# Kit_STM32.net
KiCad netlist of a schematic drawn in Altium Designer
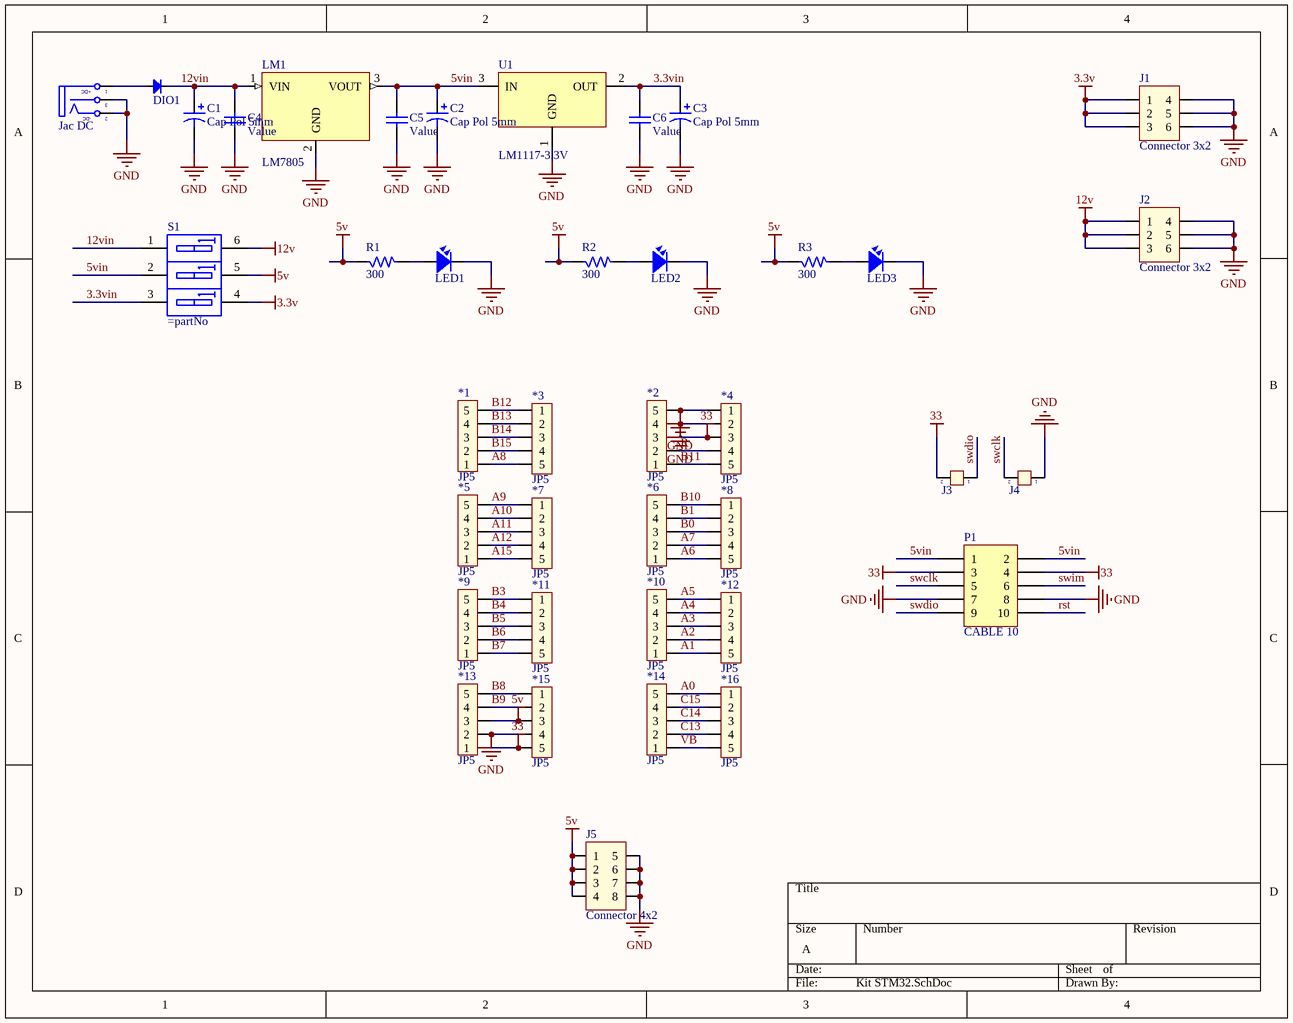
[diagram p0: Kit STM32.SchDoc]

(export (version "E")
  (design (tool "Eeschema 10.0.6"))
  (components
    (comp (ref "*1") (value "JP5") (footprint "JP5") (libsource (lib "") (part "JP5_1")))
    (comp (ref "*2") (value "JP5") (footprint "JP5") (libsource (lib "") (part "JP5_1")))
    (comp (ref "*3") (value "JP5") (footprint "JP5") (libsource (lib "Cty1") (part "JP5")))
    (comp (ref "*4") (value "JP5") (footprint "JP5") (libsource (lib "Cty1") (part "JP5")))
    (comp (ref "*5") (value "JP5") (footprint "JP5") (libsource (lib "") (part "JP5_1")))
    (comp (ref "*6") (value "JP5") (footprint "JP5") (libsource (lib "") (part "JP5_1")))
    (comp (ref "*7") (value "JP5") (footprint "JP5") (libsource (lib "Cty1") (part "JP5")))
    (comp (ref "*8") (value "JP5") (footprint "JP5") (libsource (lib "Cty1") (part "JP5")))
    (comp (ref "*9") (value "JP5") (footprint "JP5") (libsource (lib "") (part "JP5_1")))
    (comp (ref "*10") (value "JP5") (footprint "JP5") (libsource (lib "") (part "JP5_1")))
    (comp (ref "*11") (value "JP5") (footprint "JP5") (libsource (lib "Cty1") (part "JP5")))
    (comp (ref "*12") (value "JP5") (footprint "JP5") (libsource (lib "Cty1") (part "JP5")))
    (comp (ref "*13") (value "JP5") (footprint "JP5") (libsource (lib "") (part "JP5_1")))
    (comp (ref "*14") (value "JP5") (footprint "JP5") (libsource (lib "") (part "JP5_1")))
    (comp (ref "*15") (value "JP5") (footprint "JP5") (libsource (lib "Cty1") (part "JP5")))
    (comp (ref "*16") (value "JP5") (footprint "JP5") (libsource (lib "Cty1") (part "JP5")))
    (comp (ref "C1")
      (value "Cap Pol 5mm")
      (footprint "C5mm")
      (description "Polarized Capacitor (Axial)")
      (fields (field (name "PUBLISHER") "Altium Limited"))
      (libsource (lib "Cty1") (part "Cap Pol 5mm"))
    )
    (comp (ref "C2")
      (value "Cap Pol 5mm")
      (footprint "C5mm")
      (description "Polarized Capacitor (Axial)")
      (fields (field (name "PUBLISHER") "Altium Limited"))
      (libsource (lib "Cty1") (part "Cap Pol 5mm"))
    )
    (comp (ref "C3")
      (value "Cap Pol 5mm")
      (footprint "C5mm")
      (description "Polarized Capacitor (Axial)")
      (fields (field (name "PUBLISHER") "Altium Limited"))
      (libsource (lib "Cty1") (part "Cap Pol 5mm"))
    )
    (comp (ref "C4") (value "Value") (footprint "C1206") (libsource (lib "Cty1") (part "Cap SMD 1206")))
    (comp (ref "C5") (value "Value") (footprint "C1206") (libsource (lib "Cty1") (part "Cap SMD 1206")))
    (comp (ref "C6") (value "Value") (footprint "C1206") (libsource (lib "Cty1") (part "Cap SMD 1206")))
    (comp (ref "DIO1")
      (value "Diode SMD")
      (footprint "DIO-SMD-106")
      (description "Default Diode")
      (fields (field (name "PUBLISHER") "Altium Limited"))
      (libsource (lib "LIBRARY") (part "Diode SMD"))
    )
    (comp (ref "J1") (value "Connector 3x2") (footprint "JP3x2") (libsource (lib "Cty1") (part "JP3x2")))
    (comp (ref "J2") (value "Connector 3x2") (footprint "JP3x2") (libsource (lib "Cty1") (part "JP3x2")))
    (comp (ref "J3") (value "Jumper 2") (footprint "JP2") (libsource (lib "Cty1") (part "JP 2")))
    (comp (ref "J4") (value "Jumper 2") (footprint "JP2") (libsource (lib "Cty1") (part "JP 2")))
    (comp (ref "J5") (value "Connector 4x2") (footprint "JP4x2") (libsource (lib "Cty1") (part "JP4x2")))
    (comp (ref "JDC1")
      (value "Jac DC")
      (footprint "DC-IN")
      (description "Jac DC input")
      (libsource (lib "syhaunguyen") (part "DCIN"))
    )
    (comp (ref "LED1") (value "LED") (footprint "LED 3512") (libsource (lib "LIBRARY") (part "LED SMD")))
    (comp (ref "LED2") (value "LED") (footprint "LED 3512") (libsource (lib "LIBRARY") (part "LED SMD")))
    (comp (ref "LED3") (value "LED") (footprint "LED 3512") (libsource (lib "LIBRARY") (part "LED SMD")))
    (comp (ref "LM1")
      (value "LM7805")
      (footprint "QTO-220H3")
      (description "TO-220")
      (libsource (lib "Cty1") (part "LM7805"))
    )
    (comp (ref "P1")
      (value "CABLE 10")
      (footprint "CABLE 10")
      (description "Header, 5-Pin, Dual row")
      (fields (field (name "PUBLISHER") "Altium Limited"))
      (libsource (lib "Cty1") (part "CABLE 10"))
    )
    (comp (ref "R1")
      (value "300")
      (footprint "SM-1206")
      (description "Resistor 1/4W")
      (libsource (lib "Cty1") (part "Res"))
    )
    (comp (ref "R2")
      (value "300")
      (footprint "SM-1206")
      (description "Resistor 1/4W")
      (libsource (lib "Cty1") (part "Res"))
    )
    (comp (ref "R3")
      (value "300")
      (footprint "SM-1206")
      (description "Resistor 1/4W")
      (libsource (lib "Cty1") (part "Res"))
    )
    (comp (ref "S1")
      (value "~")
      (footprint "SW-DIP3")
      (description "WS-DITV 2.54 mm small compact THT flat actuator with top tape")
      (fields
        (field (name "MANUFACTURER") "Wurth Elektronik")
        (field (name "PART NO.") "418127160901")
        (field (name "CREATED BY") "Baojun Chen")
      )
      (libsource (lib "LIBRARY") (part "SWDIP3"))
    )
    (comp (ref "U1")
      (value "LM1117-3.3V")
      (footprint "SOT223-4N")
      (description "800mA Low-Dropout Linear Regulator")
      (fields (field (name "CREATOR") "Nguyen Ba Bien"))
      (libsource (lib "Cty1") (part "LM1117"))
    )
  )
  (nets
    (net (code "1") (name "/3.3vin") (class "Default")
      (node (ref "C3") (pin "1") (pinfunction "1_1") (pintype "passive"))
      (node (ref "C6") (pin "2") (pinfunction "2_2") (pintype "passive"))
      (node (ref "S1") (pin "3") (pinfunction "3_3") (pintype "passive"))
      (node (ref "U1") (pin "2") (pinfunction "OUT_2") (pintype "passive"))
    )
    (net (code "2") (name "/5vin") (class "Default")
      (node (ref "C2") (pin "1") (pinfunction "1_1") (pintype "passive"))
      (node (ref "C5") (pin "2") (pinfunction "2_2") (pintype "passive"))
      (node (ref "LM1") (pin "3") (pinfunction "VOUT_3") (pintype "output"))
      (node (ref "P1") (pin "1") (pinfunction "1_1") (pintype "passive"))
      (node (ref "P1") (pin "2") (pinfunction "2_2") (pintype "passive"))
      (node (ref "S1") (pin "2") (pinfunction "2_2") (pintype "passive"))
      (node (ref "U1") (pin "3") (pinfunction "IN_3") (pintype "passive"))
    )
    (net (code "3") (name "/12vin") (class "Default")
      (node (ref "C1") (pin "1") (pinfunction "1_1") (pintype "passive"))
      (node (ref "C4") (pin "2") (pinfunction "2_2") (pintype "passive"))
      (node (ref "DIO1") (pin "2") (pinfunction "K_2") (pintype "passive"))
      (node (ref "LM1") (pin "1") (pinfunction "VIN_1") (pintype "input"))
      (node (ref "S1") (pin "1") (pinfunction "1_1") (pintype "passive"))
    )
    (net (code "4") (name "/A0") (class "Default")
      (node (ref "*14") (pin "5") (pinfunction "5_5") (pintype "passive"))
      (node (ref "*16") (pin "1") (pinfunction "1_1") (pintype "passive"))
    )
    (net (code "5") (name "/A1") (class "Default")
      (node (ref "*10") (pin "1") (pinfunction "1_1") (pintype "passive"))
      (node (ref "*12") (pin "5") (pinfunction "5_5") (pintype "passive"))
    )
    (net (code "6") (name "/A2") (class "Default")
      (node (ref "*10") (pin "2") (pinfunction "2_2") (pintype "passive"))
      (node (ref "*12") (pin "4") (pinfunction "4_4") (pintype "passive"))
    )
    (net (code "7") (name "/A3") (class "Default")
      (node (ref "*10") (pin "3") (pinfunction "3_3") (pintype "passive"))
      (node (ref "*12") (pin "3") (pinfunction "3_3") (pintype "passive"))
    )
    (net (code "8") (name "/A4") (class "Default")
      (node (ref "*10") (pin "4") (pinfunction "4_4") (pintype "passive"))
      (node (ref "*12") (pin "2") (pinfunction "2_2") (pintype "passive"))
    )
    (net (code "9") (name "/A5") (class "Default")
      (node (ref "*10") (pin "5") (pinfunction "5_5") (pintype "passive"))
      (node (ref "*12") (pin "1") (pinfunction "1_1") (pintype "passive"))
    )
    (net (code "10") (name "/A6") (class "Default")
      (node (ref "*6") (pin "1") (pinfunction "1_1") (pintype "passive"))
      (node (ref "*8") (pin "5") (pinfunction "5_5") (pintype "passive"))
    )
    (net (code "11") (name "/A7") (class "Default")
      (node (ref "*6") (pin "2") (pinfunction "2_2") (pintype "passive"))
      (node (ref "*8") (pin "4") (pinfunction "4_4") (pintype "passive"))
    )
    (net (code "12") (name "/A8") (class "Default")
      (node (ref "*1") (pin "1") (pinfunction "1_1") (pintype "passive"))
      (node (ref "*3") (pin "5") (pinfunction "5_5") (pintype "passive"))
    )
    (net (code "13") (name "/A9") (class "Default")
      (node (ref "*5") (pin "5") (pinfunction "5_5") (pintype "passive"))
      (node (ref "*7") (pin "1") (pinfunction "1_1") (pintype "passive"))
    )
    (net (code "14") (name "/A10") (class "Default")
      (node (ref "*5") (pin "4") (pinfunction "4_4") (pintype "passive"))
      (node (ref "*7") (pin "2") (pinfunction "2_2") (pintype "passive"))
    )
    (net (code "15") (name "/A11") (class "Default")
      (node (ref "*5") (pin "3") (pinfunction "3_3") (pintype "passive"))
      (node (ref "*7") (pin "3") (pinfunction "3_3") (pintype "passive"))
    )
    (net (code "16") (name "/A12") (class "Default")
      (node (ref "*5") (pin "2") (pinfunction "2_2") (pintype "passive"))
      (node (ref "*7") (pin "4") (pinfunction "4_4") (pintype "passive"))
    )
    (net (code "17") (name "/A15") (class "Default")
      (node (ref "*5") (pin "1") (pinfunction "1_1") (pintype "passive"))
      (node (ref "*7") (pin "5") (pinfunction "5_5") (pintype "passive"))
    )
    (net (code "18") (name "/B0") (class "Default")
      (node (ref "*6") (pin "3") (pinfunction "3_3") (pintype "passive"))
      (node (ref "*8") (pin "3") (pinfunction "3_3") (pintype "passive"))
    )
    (net (code "19") (name "/B1") (class "Default")
      (node (ref "*6") (pin "4") (pinfunction "4_4") (pintype "passive"))
      (node (ref "*8") (pin "2") (pinfunction "2_2") (pintype "passive"))
    )
    (net (code "20") (name "/B3") (class "Default")
      (node (ref "*11") (pin "1") (pinfunction "1_1") (pintype "passive"))
      (node (ref "*9") (pin "5") (pinfunction "5_5") (pintype "passive"))
    )
    (net (code "21") (name "/B4") (class "Default")
      (node (ref "*11") (pin "2") (pinfunction "2_2") (pintype "passive"))
      (node (ref "*9") (pin "4") (pinfunction "4_4") (pintype "passive"))
    )
    (net (code "22") (name "/B5") (class "Default")
      (node (ref "*11") (pin "3") (pinfunction "3_3") (pintype "passive"))
      (node (ref "*9") (pin "3") (pinfunction "3_3") (pintype "passive"))
    )
    (net (code "23") (name "/B6") (class "Default")
      (node (ref "*11") (pin "4") (pinfunction "4_4") (pintype "passive"))
      (node (ref "*9") (pin "2") (pinfunction "2_2") (pintype "passive"))
    )
    (net (code "24") (name "/B7") (class "Default")
      (node (ref "*11") (pin "5") (pinfunction "5_5") (pintype "passive"))
      (node (ref "*9") (pin "1") (pinfunction "1_1") (pintype "passive"))
    )
    (net (code "25") (name "/B8") (class "Default")
      (node (ref "*13") (pin "5") (pinfunction "5_5") (pintype "passive"))
      (node (ref "*15") (pin "1") (pinfunction "1_1") (pintype "passive"))
    )
    (net (code "26") (name "/B9") (class "Default")
      (node (ref "*13") (pin "4") (pinfunction "4_4") (pintype "passive"))
      (node (ref "*15") (pin "2") (pinfunction "2_2") (pintype "passive"))
    )
    (net (code "27") (name "/B10") (class "Default")
      (node (ref "*6") (pin "5") (pinfunction "5_5") (pintype "passive"))
      (node (ref "*8") (pin "1") (pinfunction "1_1") (pintype "passive"))
    )
    (net (code "28") (name "/B11") (class "Default")
      (node (ref "*2") (pin "1") (pinfunction "1_1") (pintype "passive"))
      (node (ref "*4") (pin "5") (pinfunction "5_5") (pintype "passive"))
    )
    (net (code "29") (name "/B12") (class "Default")
      (node (ref "*1") (pin "5") (pinfunction "5_5") (pintype "passive"))
      (node (ref "*3") (pin "1") (pinfunction "1_1") (pintype "passive"))
    )
    (net (code "30") (name "/B13") (class "Default")
      (node (ref "*1") (pin "4") (pinfunction "4_4") (pintype "passive"))
      (node (ref "*3") (pin "2") (pinfunction "2_2") (pintype "passive"))
    )
    (net (code "31") (name "/B14") (class "Default")
      (node (ref "*1") (pin "3") (pinfunction "3_3") (pintype "passive"))
      (node (ref "*3") (pin "3") (pinfunction "3_3") (pintype "passive"))
    )
    (net (code "32") (name "/B15") (class "Default")
      (node (ref "*1") (pin "2") (pinfunction "2_2") (pintype "passive"))
      (node (ref "*3") (pin "4") (pinfunction "4_4") (pintype "passive"))
    )
    (net (code "33") (name "/C13") (class "Default")
      (node (ref "*14") (pin "2") (pinfunction "2_2") (pintype "passive"))
      (node (ref "*16") (pin "4") (pinfunction "4_4") (pintype "passive"))
    )
    (net (code "34") (name "/C14") (class "Default")
      (node (ref "*14") (pin "3") (pinfunction "3_3") (pintype "passive"))
      (node (ref "*16") (pin "3") (pinfunction "3_3") (pintype "passive"))
    )
    (net (code "35") (name "/C15") (class "Default")
      (node (ref "*14") (pin "4") (pinfunction "4_4") (pintype "passive"))
      (node (ref "*16") (pin "2") (pinfunction "2_2") (pintype "passive"))
    )
    (net (code "36") (name "/R") (class "Default")
      (node (ref "*2") (pin "2") (pinfunction "2_2") (pintype "passive"))
      (node (ref "*4") (pin "4") (pinfunction "4_4") (pintype "passive"))
    )
    (net (code "37") (name "/VB") (class "Default")
      (node (ref "*14") (pin "1") (pinfunction "1_1") (pintype "passive"))
      (node (ref "*16") (pin "5") (pinfunction "5_5") (pintype "passive"))
    )
    (net (code "38") (name "/rst") (class "Default")
      (node (ref "P1") (pin "10") (pinfunction "10_10") (pintype "passive"))
    )
    (net (code "39") (name "/swclk") (class "Default")
      (node (ref "J4") (pin "2") (pinfunction "2_2") (pintype "passive"))
      (node (ref "P1") (pin "5") (pinfunction "5_5") (pintype "passive"))
    )
    (net (code "40") (name "/swdio") (class "Default")
      (node (ref "J3") (pin "1") (pinfunction "1_1") (pintype "passive"))
      (node (ref "P1") (pin "9") (pinfunction "9_9") (pintype "passive"))
    )
    (net (code "41") (name "/swim") (class "Default")
      (node (ref "P1") (pin "6") (pinfunction "6_6") (pintype "passive"))
    )
    (net (code "42") (name "3.3v") (class "Default")
      (node (ref "J1") (pin "1") (pinfunction "1_1") (pintype "passive"))
      (node (ref "J1") (pin "2") (pinfunction "2_2") (pintype "passive"))
      (node (ref "J1") (pin "3") (pinfunction "3_3") (pintype "passive"))
      (node (ref "S1") (pin "4") (pinfunction "4_4") (pintype "passive"))
    )
    (net (code "43") (name "5v") (class "Default")
      (node (ref "*13") (pin "3") (pinfunction "3_3") (pintype "passive"))
      (node (ref "*15") (pin "3") (pinfunction "3_3") (pintype "passive"))
      (node (ref "J5") (pin "1") (pinfunction "1_1") (pintype "passive"))
      (node (ref "J5") (pin "2") (pinfunction "2_2") (pintype "passive"))
      (node (ref "J5") (pin "3") (pinfunction "3_3") (pintype "passive"))
      (node (ref "J5") (pin "4") (pinfunction "4_4") (pintype "passive"))
      (node (ref "R1") (pin "1") (pinfunction "1_1") (pintype "passive"))
      (node (ref "R2") (pin "1") (pinfunction "1_1") (pintype "passive"))
      (node (ref "R3") (pin "1") (pinfunction "1_1") (pintype "passive"))
      (node (ref "S1") (pin "5") (pinfunction "5_5") (pintype "passive"))
    )
    (net (code "44") (name "12v") (class "Default")
      (node (ref "J2") (pin "1") (pinfunction "1_1") (pintype "passive"))
      (node (ref "J2") (pin "2") (pinfunction "2_2") (pintype "passive"))
      (node (ref "J2") (pin "3") (pinfunction "3_3") (pintype "passive"))
      (node (ref "S1") (pin "6") (pinfunction "6_6") (pintype "passive"))
    )
    (net (code "45") (name "33") (class "Default")
      (node (ref "*13") (pin "1") (pinfunction "1_1") (pintype "passive"))
      (node (ref "*15") (pin "5") (pinfunction "5_5") (pintype "passive"))
      (node (ref "*2") (pin "3") (pinfunction "3_3") (pintype "passive"))
      (node (ref "*4") (pin "3") (pinfunction "3_3") (pintype "passive"))
      (node (ref "J3") (pin "2") (pinfunction "2_2") (pintype "passive"))
      (node (ref "P1") (pin "3") (pinfunction "3_3") (pintype "passive"))
      (node (ref "P1") (pin "4") (pinfunction "4_4") (pintype "passive"))
    )
    (net (code "46") (name "GND") (class "Default")
      (node (ref "*13") (pin "2") (pinfunction "2_2") (pintype "passive"))
      (node (ref "*15") (pin "4") (pinfunction "4_4") (pintype "passive"))
      (node (ref "*2") (pin "4") (pinfunction "4_4") (pintype "passive"))
      (node (ref "*2") (pin "5") (pinfunction "5_5") (pintype "passive"))
      (node (ref "*4") (pin "1") (pinfunction "1_1") (pintype "passive"))
      (node (ref "*4") (pin "2") (pinfunction "2_2") (pintype "passive"))
      (node (ref "C1") (pin "2") (pinfunction "2_2") (pintype "passive"))
      (node (ref "C2") (pin "2") (pinfunction "2_2") (pintype "passive"))
      (node (ref "C3") (pin "2") (pinfunction "2_2") (pintype "passive"))
      (node (ref "C4") (pin "1") (pinfunction "1_1") (pintype "passive"))
      (node (ref "C5") (pin "1") (pinfunction "1_1") (pintype "passive"))
      (node (ref "C6") (pin "1") (pinfunction "1_1") (pintype "passive"))
      (node (ref "J1") (pin "4") (pinfunction "4_4") (pintype "passive"))
      (node (ref "J1") (pin "5") (pinfunction "5_5") (pintype "passive"))
      (node (ref "J1") (pin "6") (pinfunction "6_6") (pintype "passive"))
      (node (ref "J2") (pin "4") (pinfunction "4_4") (pintype "passive"))
      (node (ref "J2") (pin "5") (pinfunction "5_5") (pintype "passive"))
      (node (ref "J2") (pin "6") (pinfunction "6_6") (pintype "passive"))
      (node (ref "J4") (pin "1") (pinfunction "1_1") (pintype "passive"))
      (node (ref "J5") (pin "5") (pinfunction "5_5") (pintype "passive"))
      (node (ref "J5") (pin "6") (pinfunction "6_6") (pintype "passive"))
      (node (ref "J5") (pin "7") (pinfunction "7_7") (pintype "passive"))
      (node (ref "J5") (pin "8") (pinfunction "8_8") (pintype "passive"))
      (node (ref "JDC1") (pin "2") (pinfunction "TN_2") (pintype "passive"))
      (node (ref "JDC1") (pin "3") (pinfunction "S_3") (pintype "power_in"))
      (node (ref "LED1") (pin "2") (pinfunction "2_2") (pintype "passive"))
      (node (ref "LED2") (pin "2") (pinfunction "2_2") (pintype "passive"))
      (node (ref "LED3") (pin "2") (pinfunction "2_2") (pintype "passive"))
      (node (ref "LM1") (pin "2") (pinfunction "GND_2") (pintype "power_in"))
      (node (ref "P1") (pin "7") (pinfunction "7_7") (pintype "passive"))
      (node (ref "P1") (pin "8") (pinfunction "8_8") (pintype "passive"))
      (node (ref "U1") (pin "1") (pinfunction "GND_1") (pintype "passive"))
    )
    (net (code "47") (name "Net-(DIO1-A)") (class "Default")
      (node (ref "DIO1") (pin "1") (pinfunction "A_1") (pintype "passive"))
      (node (ref "JDC1") (pin "1") (pinfunction "T_1") (pintype "passive"))
    )
    (net (code "48") (name "Net-(LED1-Pad1)") (class "Default")
      (node (ref "LED1") (pin "1") (pinfunction "1_1") (pintype "passive"))
      (node (ref "R1") (pin "2") (pinfunction "2_2") (pintype "passive"))
    )
    (net (code "49") (name "Net-(LED2-Pad1)") (class "Default")
      (node (ref "LED2") (pin "1") (pinfunction "1_1") (pintype "passive"))
      (node (ref "R2") (pin "2") (pinfunction "2_2") (pintype "passive"))
    )
    (net (code "50") (name "Net-(LED3-Pad1)") (class "Default")
      (node (ref "LED3") (pin "1") (pinfunction "1_1") (pintype "passive"))
      (node (ref "R3") (pin "2") (pinfunction "2_2") (pintype "passive"))
    )
  )
)
